# Power.net
KiCad netlist of a schematic drawn in Altium Designer
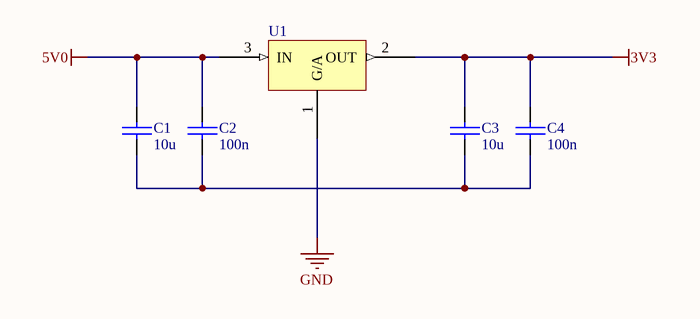
[diagram p0: Power.SchDoc]

(export (version "E")
  (design (tool "Eeschema 10.0.6"))
  (components
    (comp (ref "C1")
      (value "10u")
      (footprint "C0805")
      (description "电容")
      (libsource (lib "LQ_Integrated_Library") (part "Capacitor"))
    )
    (comp (ref "C2")
      (value "100n")
      (footprint "C0603")
      (description "电容")
      (libsource (lib "LQ_Integrated_Library") (part "Capacitor"))
    )
    (comp (ref "C3")
      (value "10u")
      (footprint "C0805")
      (description "电容")
      (libsource (lib "LQ_Integrated_Library") (part "Capacitor"))
    )
    (comp (ref "C4")
      (value "100n")
      (footprint "C0603")
      (description "电容")
      (libsource (lib "LQ_Integrated_Library") (part "Capacitor"))
    )
    (comp (ref "U1")
      (value "AMS1117-XX")
      (footprint "SOT223")
      (description "稳压芯片")
      (libsource (lib "LQ_Integrated_Library") (part "AMS1117-XX"))
    )
  )
  (nets
    (net (code "1") (name "3V3") (class "Default")
      (node (ref "C3") (pin "1") (pinfunction "1_1") (pintype "passive"))
      (node (ref "C4") (pin "1") (pinfunction "1_1") (pintype "passive"))
      (node (ref "U1") (pin "2") (pinfunction "OUT_2") (pintype "output"))
    )
    (net (code "2") (name "5V0") (class "Default")
      (node (ref "C1") (pin "1") (pinfunction "1_1") (pintype "passive"))
      (node (ref "C2") (pin "1") (pinfunction "1_1") (pintype "passive"))
      (node (ref "U1") (pin "3") (pinfunction "IN_3") (pintype "input"))
    )
    (net (code "3") (name "GND") (class "Default")
      (node (ref "U1") (pin "1") (pinfunction "G/A_1") (pintype "passive"))
    )
    (net (code "4") (name "Net-(C1-Pad2)") (class "Default")
      (node (ref "C1") (pin "2") (pinfunction "2_2") (pintype "passive"))
      (node (ref "C2") (pin "2") (pinfunction "2_2") (pintype "passive"))
      (node (ref "C3") (pin "2") (pinfunction "2_2") (pintype "passive"))
      (node (ref "C4") (pin "2") (pinfunction "2_2") (pintype "passive"))
    )
  )
)
